# DD2090_4CAM_FFC_MIPI_4LANE_CAM.net
KiCad netlist of a schematic drawn in Altium Designer
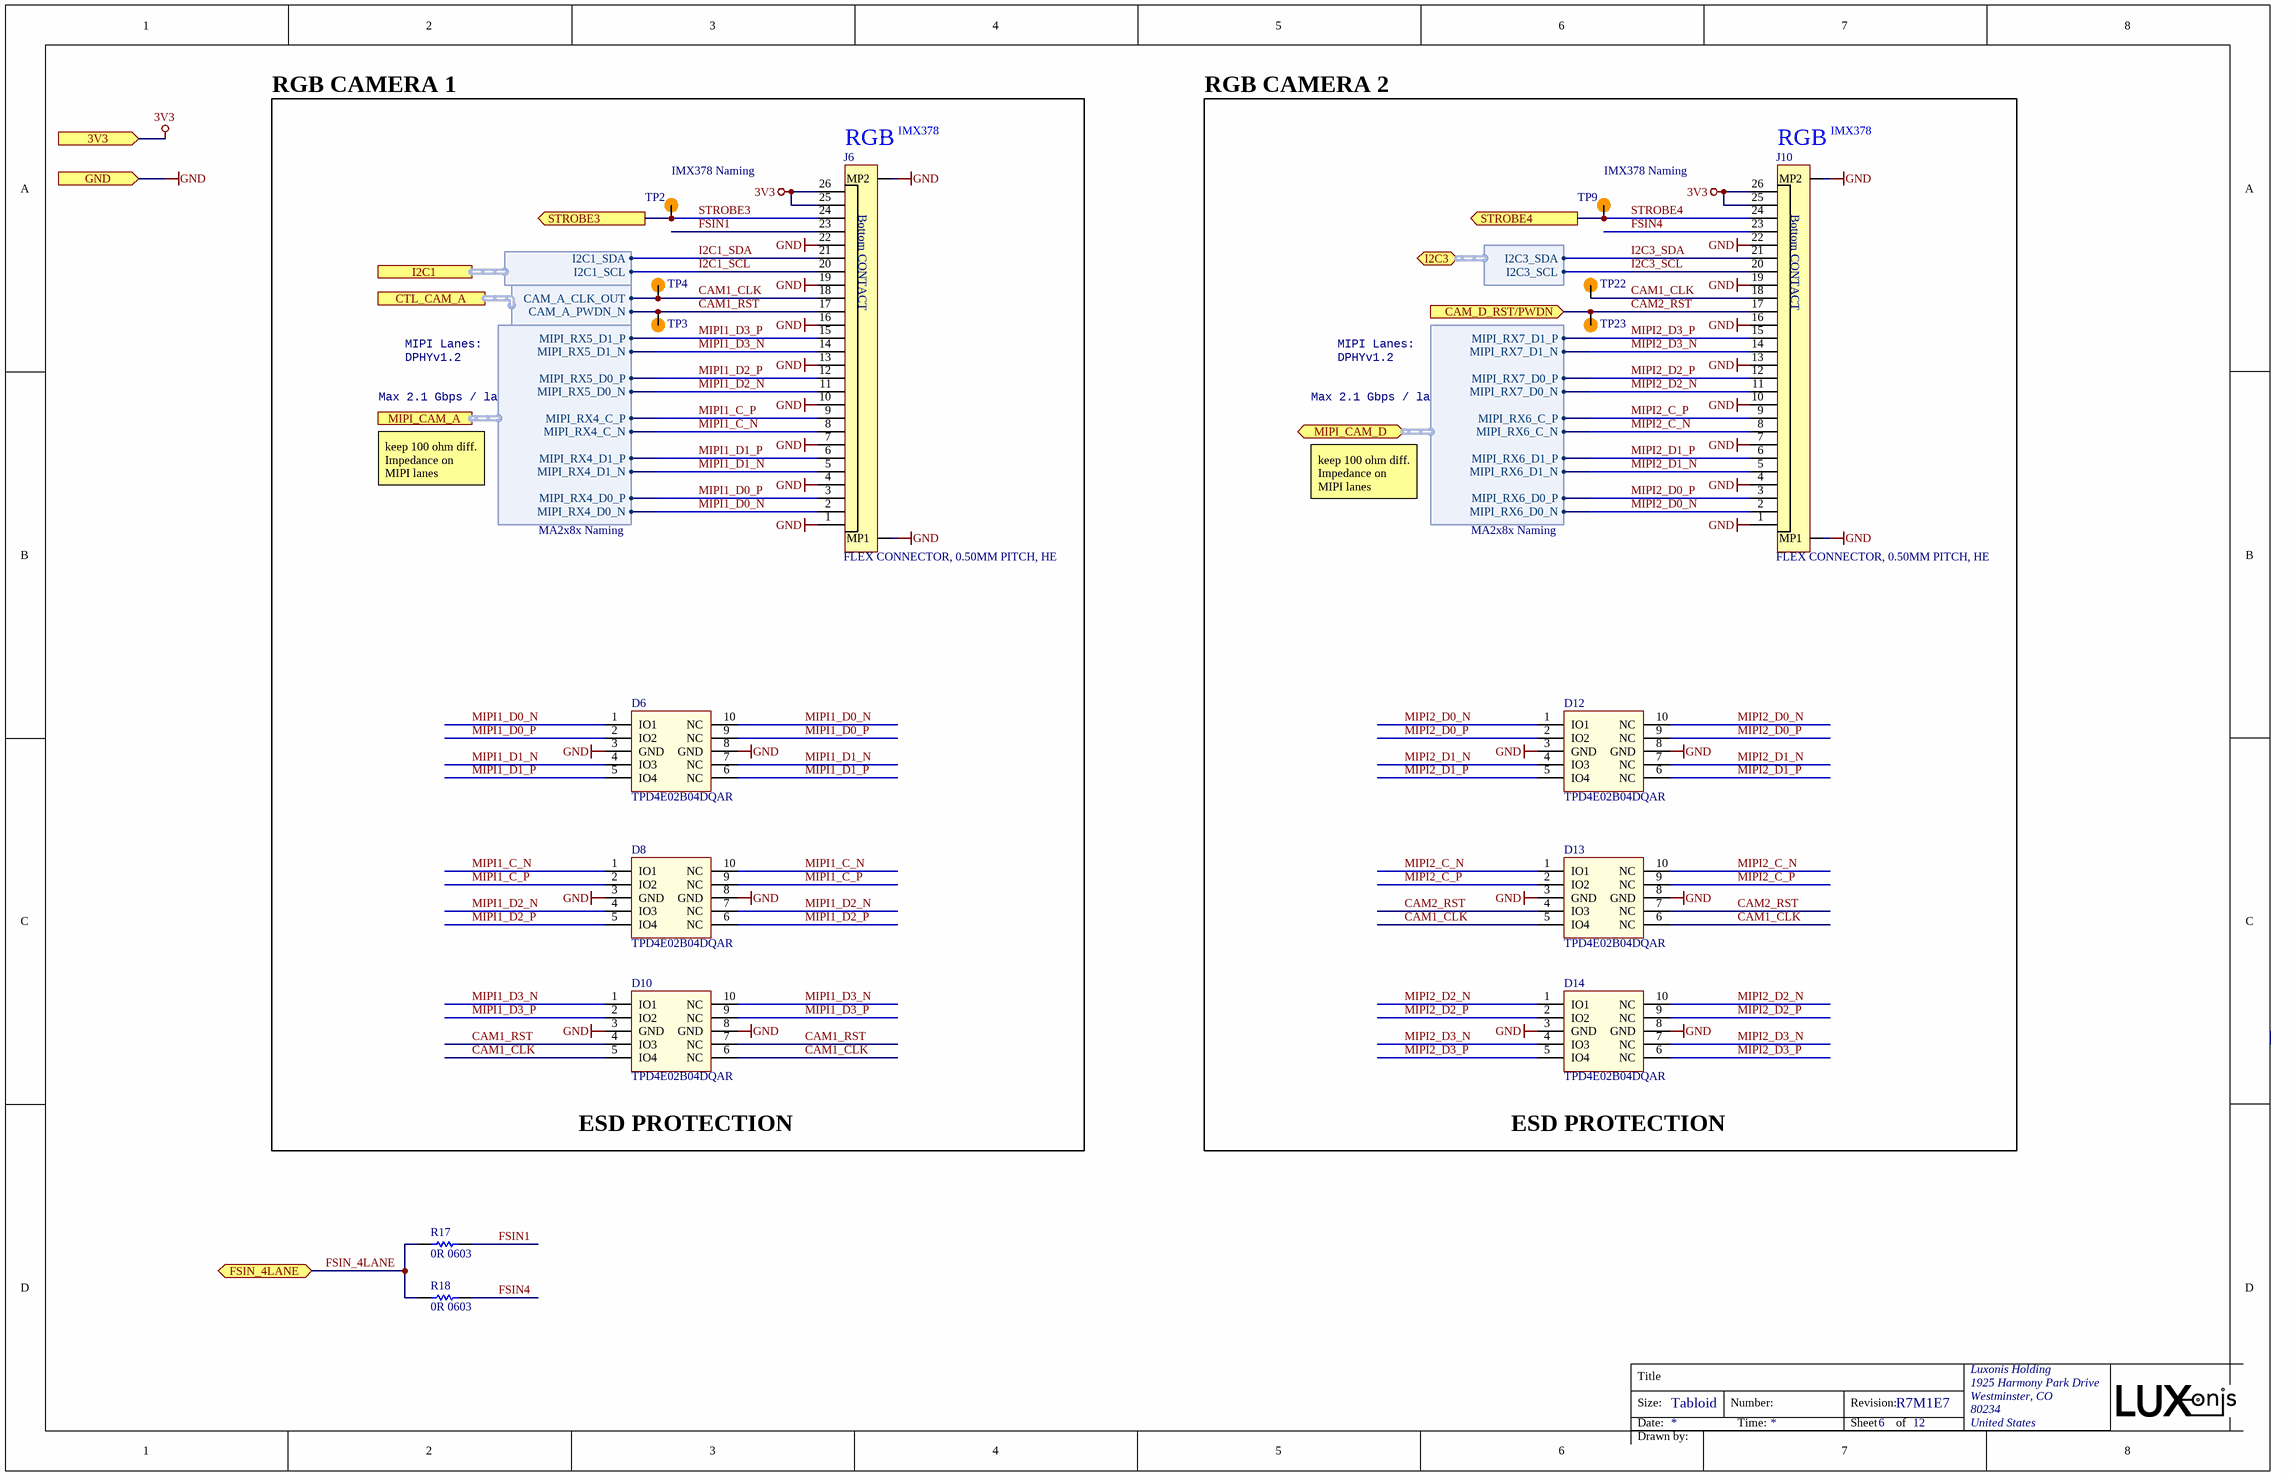
[diagram p0: DD2090_4CAM_FFC_MIPI_4LANE_CAM.SchDoc]

(export (version "E")
  (design (tool "Eeschema 10.0.6"))
  (components
    (comp (ref "D6")
      (value "TPD4E02B04DQAR")
      (footprint "LuxonisMaster:TPD4E02B04DQAR")
      (libsource (lib "LuxonisMaster") (part "TPD4E02B04DQAR"))
    )
    (comp (ref "D8")
      (value "TPD4E02B04DQAR")
      (footprint "LuxonisMaster:TPD4E02B04DQAR")
      (libsource (lib "LuxonisMaster") (part "TPD4E02B04DQAR"))
    )
    (comp (ref "D10")
      (value "TPD4E02B04DQAR")
      (footprint "LuxonisMaster:TPD4E02B04DQAR")
      (libsource (lib "LuxonisMaster") (part "TPD4E02B04DQAR"))
    )
    (comp (ref "D12")
      (value "TPD4E02B04DQAR")
      (footprint "TPD4E02B04DQAR")
      (libsource (lib "LuxonisMaster") (part "TPD4E02B04DQAR"))
    )
    (comp (ref "D13")
      (value "TPD4E02B04DQAR")
      (footprint "TPD4E02B04DQAR")
      (libsource (lib "LuxonisMaster") (part "TPD4E02B04DQAR"))
    )
    (comp (ref "D14")
      (value "TPD4E02B04DQAR")
      (footprint "TPD4E02B04DQAR")
      (libsource (lib "LuxonisMaster") (part "TPD4E02B04DQAR"))
    )
    (comp (ref "J6")
      (value "FLEX CONNECTOR, 0.50MM PITCH, HE")
      (footprint "DM1090FFC:F32R-1A7H1-11026")
      (description "26 Position FFC, FPC Connector Contacts, Bottom 0.020\" (0.50mm) Surface Mount, Right Angle")
      (libsource (lib "DM1090FFC") (part "F32R-1A7H1-11026"))
    )
    (comp (ref "J10")
      (value "FLEX CONNECTOR, 0.50MM PITCH, HE")
      (footprint "DM1090FFC:F32R-1A7H1-11026")
      (description "26 Position FFC, FPC Connector Contacts, Bottom 0.020\" (0.50mm) Surface Mount, Right Angle")
      (libsource (lib "DM1090FFC") (part "F32R-1A7H1-11026"))
    )
    (comp (ref "R17")
      (value "0R 0603")
      (footprint "RESC0603(1608)_N")
      (fields (field (name "TOLERANCE") "5%"))
      (libsource (lib "LuxonisMaster") (part "CRCW06030000Z0EA"))
    )
    (comp (ref "R18")
      (value "0R 0603")
      (footprint "RESC0603(1608)_N")
      (fields (field (name "TOLERANCE") "5%"))
      (libsource (lib "LuxonisMaster") (part "CRCW06030000Z0EA"))
    )
    (comp (ref "TP2")
      (value "TP100_200_NS")
      (footprint "LuxonisMaster:TP100_200_NS")
      (libsource (lib "LuxonisMaster") (part "TEST_POINT"))
    )
    (comp (ref "TP3")
      (value "TP100_200_NS")
      (footprint "LuxonisMaster:TP100_200_NS")
      (libsource (lib "LuxonisMaster") (part "TEST_POINT"))
    )
    (comp (ref "TP4")
      (value "TP100_200_NS")
      (footprint "LuxonisMaster:TP100_200_NS")
      (libsource (lib "LuxonisMaster") (part "TEST_POINT"))
    )
    (comp (ref "TP9")
      (value "TP100_200_NS")
      (footprint "LuxonisMaster:TP100_200_NS")
      (libsource (lib "LuxonisMaster") (part "TEST_POINT"))
    )
    (comp (ref "TP22")
      (value "TP100_200_NS")
      (footprint "TP100_200_NS")
      (libsource (lib "LuxonisMaster") (part "TEST_POINT"))
    )
    (comp (ref "TP23")
      (value "TP100_200_NS")
      (footprint "TP100_200_NS")
      (libsource (lib "LuxonisMaster") (part "TEST_POINT"))
    )
  )
  (nets
    (net (code "6") (name "/CAM1_CLK") (class "Default")
      (node (ref "D10") (pin "5") (pinfunction "IO4_5") (pintype "passive"))
      (node (ref "D10") (pin "6") (pinfunction "NC_6") (pintype "passive"))
      (node (ref "D13") (pin "5") (pinfunction "IO4_5") (pintype "passive"))
      (node (ref "D13") (pin "6") (pinfunction "NC_6") (pintype "passive"))
      (node (ref "J10") (pin "18") (pinfunction "18_18") (pintype "passive"))
      (node (ref "J6") (pin "18") (pinfunction "18_18") (pintype "passive"))
      (node (ref "TP22") (pin "1") (pintype "passive"))
      (node (ref "TP4") (pin "1") (pintype "passive"))
    )
    (net (code "7") (name "/CAM1_RST") (class "Default")
      (node (ref "D10") (pin "4") (pinfunction "IO3_4") (pintype "passive"))
      (node (ref "D10") (pin "7") (pinfunction "NC_7") (pintype "passive"))
      (node (ref "J6") (pin "17") (pinfunction "17_17") (pintype "passive"))
      (node (ref "TP3") (pin "1") (pintype "passive"))
    )
    (net (code "8") (name "/CAM2_RST") (class "Default")
      (node (ref "D13") (pin "4") (pinfunction "IO3_4") (pintype "passive"))
      (node (ref "D13") (pin "7") (pinfunction "NC_7") (pintype "passive"))
      (node (ref "J10") (pin "17") (pinfunction "17_17") (pintype "passive"))
      (node (ref "TP23") (pin "1") (pintype "passive"))
    )
    (net (code "10") (name "/FSIN1") (class "Default")
      (node (ref "J6") (pin "23") (pinfunction "23_23") (pintype "passive"))
      (node (ref "R17") (pin "2") (pinfunction "2_2") (pintype "passive"))
    )
    (net (code "11") (name "/FSIN4") (class "Default")
      (node (ref "J10") (pin "23") (pinfunction "23_23") (pintype "passive"))
      (node (ref "R18") (pin "2") (pinfunction "2_2") (pintype "passive"))
    )
    (net (code "12") (name "/FSIN_4LANE") (class "Default")
      (node (ref "R17") (pin "1") (pinfunction "1_1") (pintype "passive"))
      (node (ref "R18") (pin "1") (pinfunction "1_1") (pintype "passive"))
    )
    (net (code "13") (name "/I2C1_SCL") (class "Default")
      (node (ref "J6") (pin "20") (pinfunction "20_20") (pintype "passive"))
    )
    (net (code "14") (name "/I2C1_SDA") (class "Default")
      (node (ref "J6") (pin "21") (pinfunction "21_21") (pintype "passive"))
    )
    (net (code "16") (name "/I2C3_SCL") (class "Default")
      (node (ref "J10") (pin "20") (pinfunction "20_20") (pintype "passive"))
    )
    (net (code "17") (name "/I2C3_SDA") (class "Default")
      (node (ref "J10") (pin "21") (pinfunction "21_21") (pintype "passive"))
    )
    (net (code "18") (name "/MIPI1_C_N") (class "Default")
      (node (ref "D8") (pin "1") (pinfunction "IO1_1") (pintype "passive"))
      (node (ref "D8") (pin "10") (pinfunction "NC_10") (pintype "passive"))
      (node (ref "J6") (pin "8") (pinfunction "8_8") (pintype "passive"))
    )
    (net (code "19") (name "/MIPI1_C_P") (class "Default")
      (node (ref "D8") (pin "2") (pinfunction "IO2_2") (pintype "passive"))
      (node (ref "D8") (pin "9") (pinfunction "NC_9") (pintype "passive"))
      (node (ref "J6") (pin "9") (pinfunction "9_9") (pintype "passive"))
    )
    (net (code "20") (name "/MIPI1_D0_N") (class "Default")
      (node (ref "D6") (pin "1") (pinfunction "IO1_1") (pintype "passive"))
      (node (ref "D6") (pin "10") (pinfunction "NC_10") (pintype "passive"))
      (node (ref "J6") (pin "2") (pinfunction "2_2") (pintype "passive"))
    )
    (net (code "21") (name "/MIPI1_D0_P") (class "Default")
      (node (ref "D6") (pin "2") (pinfunction "IO2_2") (pintype "passive"))
      (node (ref "D6") (pin "9") (pinfunction "NC_9") (pintype "passive"))
      (node (ref "J6") (pin "3") (pinfunction "3_3") (pintype "passive"))
    )
    (net (code "22") (name "/MIPI1_D1_N") (class "Default")
      (node (ref "D6") (pin "4") (pinfunction "IO3_4") (pintype "passive"))
      (node (ref "D6") (pin "7") (pinfunction "NC_7") (pintype "passive"))
      (node (ref "J6") (pin "5") (pinfunction "5_5") (pintype "passive"))
    )
    (net (code "23") (name "/MIPI1_D1_P") (class "Default")
      (node (ref "D6") (pin "5") (pinfunction "IO4_5") (pintype "passive"))
      (node (ref "D6") (pin "6") (pinfunction "NC_6") (pintype "passive"))
      (node (ref "J6") (pin "6") (pinfunction "6_6") (pintype "passive"))
    )
    (net (code "24") (name "/MIPI1_D2_N") (class "Default")
      (node (ref "D8") (pin "4") (pinfunction "IO3_4") (pintype "passive"))
      (node (ref "D8") (pin "7") (pinfunction "NC_7") (pintype "passive"))
      (node (ref "J6") (pin "11") (pinfunction "11_11") (pintype "passive"))
    )
    (net (code "25") (name "/MIPI1_D2_P") (class "Default")
      (node (ref "D8") (pin "5") (pinfunction "IO4_5") (pintype "passive"))
      (node (ref "D8") (pin "6") (pinfunction "NC_6") (pintype "passive"))
      (node (ref "J6") (pin "12") (pinfunction "12_12") (pintype "passive"))
    )
    (net (code "26") (name "/MIPI1_D3_N") (class "Default")
      (node (ref "D10") (pin "1") (pinfunction "IO1_1") (pintype "passive"))
      (node (ref "D10") (pin "10") (pinfunction "NC_10") (pintype "passive"))
      (node (ref "J6") (pin "14") (pinfunction "14_14") (pintype "passive"))
    )
    (net (code "27") (name "/MIPI1_D3_P") (class "Default")
      (node (ref "D10") (pin "2") (pinfunction "IO2_2") (pintype "passive"))
      (node (ref "D10") (pin "9") (pinfunction "NC_9") (pintype "passive"))
      (node (ref "J6") (pin "15") (pinfunction "15_15") (pintype "passive"))
    )
    (net (code "28") (name "/MIPI2_C_N") (class "Default")
      (node (ref "D13") (pin "1") (pinfunction "IO1_1") (pintype "passive"))
      (node (ref "D13") (pin "10") (pinfunction "NC_10") (pintype "passive"))
      (node (ref "J10") (pin "8") (pinfunction "8_8") (pintype "passive"))
    )
    (net (code "29") (name "/MIPI2_C_P") (class "Default")
      (node (ref "D13") (pin "2") (pinfunction "IO2_2") (pintype "passive"))
      (node (ref "D13") (pin "9") (pinfunction "NC_9") (pintype "passive"))
      (node (ref "J10") (pin "9") (pinfunction "9_9") (pintype "passive"))
    )
    (net (code "30") (name "/MIPI2_D0_N") (class "Default")
      (node (ref "D12") (pin "1") (pinfunction "IO1_1") (pintype "passive"))
      (node (ref "D12") (pin "10") (pinfunction "NC_10") (pintype "passive"))
      (node (ref "J10") (pin "2") (pinfunction "2_2") (pintype "passive"))
    )
    (net (code "31") (name "/MIPI2_D0_P") (class "Default")
      (node (ref "D12") (pin "2") (pinfunction "IO2_2") (pintype "passive"))
      (node (ref "D12") (pin "9") (pinfunction "NC_9") (pintype "passive"))
      (node (ref "J10") (pin "3") (pinfunction "3_3") (pintype "passive"))
    )
    (net (code "32") (name "/MIPI2_D1_N") (class "Default")
      (node (ref "D12") (pin "4") (pinfunction "IO3_4") (pintype "passive"))
      (node (ref "D12") (pin "7") (pinfunction "NC_7") (pintype "passive"))
      (node (ref "J10") (pin "5") (pinfunction "5_5") (pintype "passive"))
    )
    (net (code "33") (name "/MIPI2_D1_P") (class "Default")
      (node (ref "D12") (pin "5") (pinfunction "IO4_5") (pintype "passive"))
      (node (ref "D12") (pin "6") (pinfunction "NC_6") (pintype "passive"))
      (node (ref "J10") (pin "6") (pinfunction "6_6") (pintype "passive"))
    )
    (net (code "34") (name "/MIPI2_D2_N") (class "Default")
      (node (ref "D14") (pin "1") (pinfunction "IO1_1") (pintype "passive"))
      (node (ref "D14") (pin "10") (pinfunction "NC_10") (pintype "passive"))
      (node (ref "J10") (pin "11") (pinfunction "11_11") (pintype "passive"))
    )
    (net (code "35") (name "/MIPI2_D2_P") (class "Default")
      (node (ref "D14") (pin "2") (pinfunction "IO2_2") (pintype "passive"))
      (node (ref "D14") (pin "9") (pinfunction "NC_9") (pintype "passive"))
      (node (ref "J10") (pin "12") (pinfunction "12_12") (pintype "passive"))
    )
    (net (code "36") (name "/MIPI2_D3_N") (class "Default")
      (node (ref "D14") (pin "4") (pinfunction "IO3_4") (pintype "passive"))
      (node (ref "D14") (pin "7") (pinfunction "NC_7") (pintype "passive"))
      (node (ref "J10") (pin "14") (pinfunction "14_14") (pintype "passive"))
    )
    (net (code "37") (name "/MIPI2_D3_P") (class "Default")
      (node (ref "D14") (pin "5") (pinfunction "IO4_5") (pintype "passive"))
      (node (ref "D14") (pin "6") (pinfunction "NC_6") (pintype "passive"))
      (node (ref "J10") (pin "15") (pinfunction "15_15") (pintype "passive"))
    )
    (net (code "38") (name "/STROBE3") (class "Default")
      (node (ref "J6") (pin "24") (pinfunction "24_24") (pintype "passive"))
      (node (ref "TP2") (pin "1") (pintype "passive"))
    )
    (net (code "39") (name "/STROBE4") (class "Default")
      (node (ref "J10") (pin "24") (pinfunction "24_24") (pintype "passive"))
      (node (ref "TP9") (pin "1") (pintype "passive"))
    )
    (net (code "43") (name "3V3") (class "Default")
      (node (ref "J10") (pin "25") (pinfunction "25_25") (pintype "passive"))
      (node (ref "J10") (pin "26") (pinfunction "26_26") (pintype "passive"))
      (node (ref "J6") (pin "25") (pinfunction "25_25") (pintype "passive"))
      (node (ref "J6") (pin "26") (pinfunction "26_26") (pintype "passive"))
    )
    (net (code "44") (name "GND") (class "Default")
      (node (ref "D10") (pin "3") (pinfunction "GND_3") (pintype "passive"))
      (node (ref "D10") (pin "8") (pinfunction "GND_8") (pintype "passive"))
      (node (ref "D12") (pin "3") (pinfunction "GND_3") (pintype "passive"))
      (node (ref "D12") (pin "8") (pinfunction "GND_8") (pintype "passive"))
      (node (ref "D13") (pin "3") (pinfunction "GND_3") (pintype "passive"))
      (node (ref "D13") (pin "8") (pinfunction "GND_8") (pintype "passive"))
      (node (ref "D14") (pin "3") (pinfunction "GND_3") (pintype "passive"))
      (node (ref "D14") (pin "8") (pinfunction "GND_8") (pintype "passive"))
      (node (ref "D6") (pin "3") (pinfunction "GND_3") (pintype "passive"))
      (node (ref "D6") (pin "8") (pinfunction "GND_8") (pintype "passive"))
      (node (ref "D8") (pin "3") (pinfunction "GND_3") (pintype "passive"))
      (node (ref "D8") (pin "8") (pinfunction "GND_8") (pintype "passive"))
      (node (ref "J10") (pin "1") (pinfunction "1_1") (pintype "passive"))
      (node (ref "J10") (pin "10") (pinfunction "10_10") (pintype "passive"))
      (node (ref "J10") (pin "13") (pinfunction "13_13") (pintype "passive"))
      (node (ref "J10") (pin "16") (pinfunction "16_16") (pintype "passive"))
      (node (ref "J10") (pin "19") (pinfunction "19_19") (pintype "passive"))
      (node (ref "J10") (pin "22") (pinfunction "22_22") (pintype "passive"))
      (node (ref "J10") (pin "4") (pinfunction "4_4") (pintype "passive"))
      (node (ref "J10") (pin "7") (pinfunction "7_7") (pintype "passive"))
      (node (ref "J10") (pin "MP1") (pinfunction "MP1_MP1") (pintype "passive"))
      (node (ref "J10") (pin "MP2") (pinfunction "MP2_MP2") (pintype "passive"))
      (node (ref "J6") (pin "1") (pinfunction "1_1") (pintype "passive"))
      (node (ref "J6") (pin "10") (pinfunction "10_10") (pintype "passive"))
      (node (ref "J6") (pin "13") (pinfunction "13_13") (pintype "passive"))
      (node (ref "J6") (pin "16") (pinfunction "16_16") (pintype "passive"))
      (node (ref "J6") (pin "19") (pinfunction "19_19") (pintype "passive"))
      (node (ref "J6") (pin "22") (pinfunction "22_22") (pintype "passive"))
      (node (ref "J6") (pin "4") (pinfunction "4_4") (pintype "passive"))
      (node (ref "J6") (pin "7") (pinfunction "7_7") (pintype "passive"))
      (node (ref "J6") (pin "MP1") (pinfunction "MP1_MP1") (pintype "passive"))
      (node (ref "J6") (pin "MP2") (pinfunction "MP2_MP2") (pintype "passive"))
    )
  )
)
